# Ethernet.net
KiCad netlist of a schematic drawn in Altium Designer
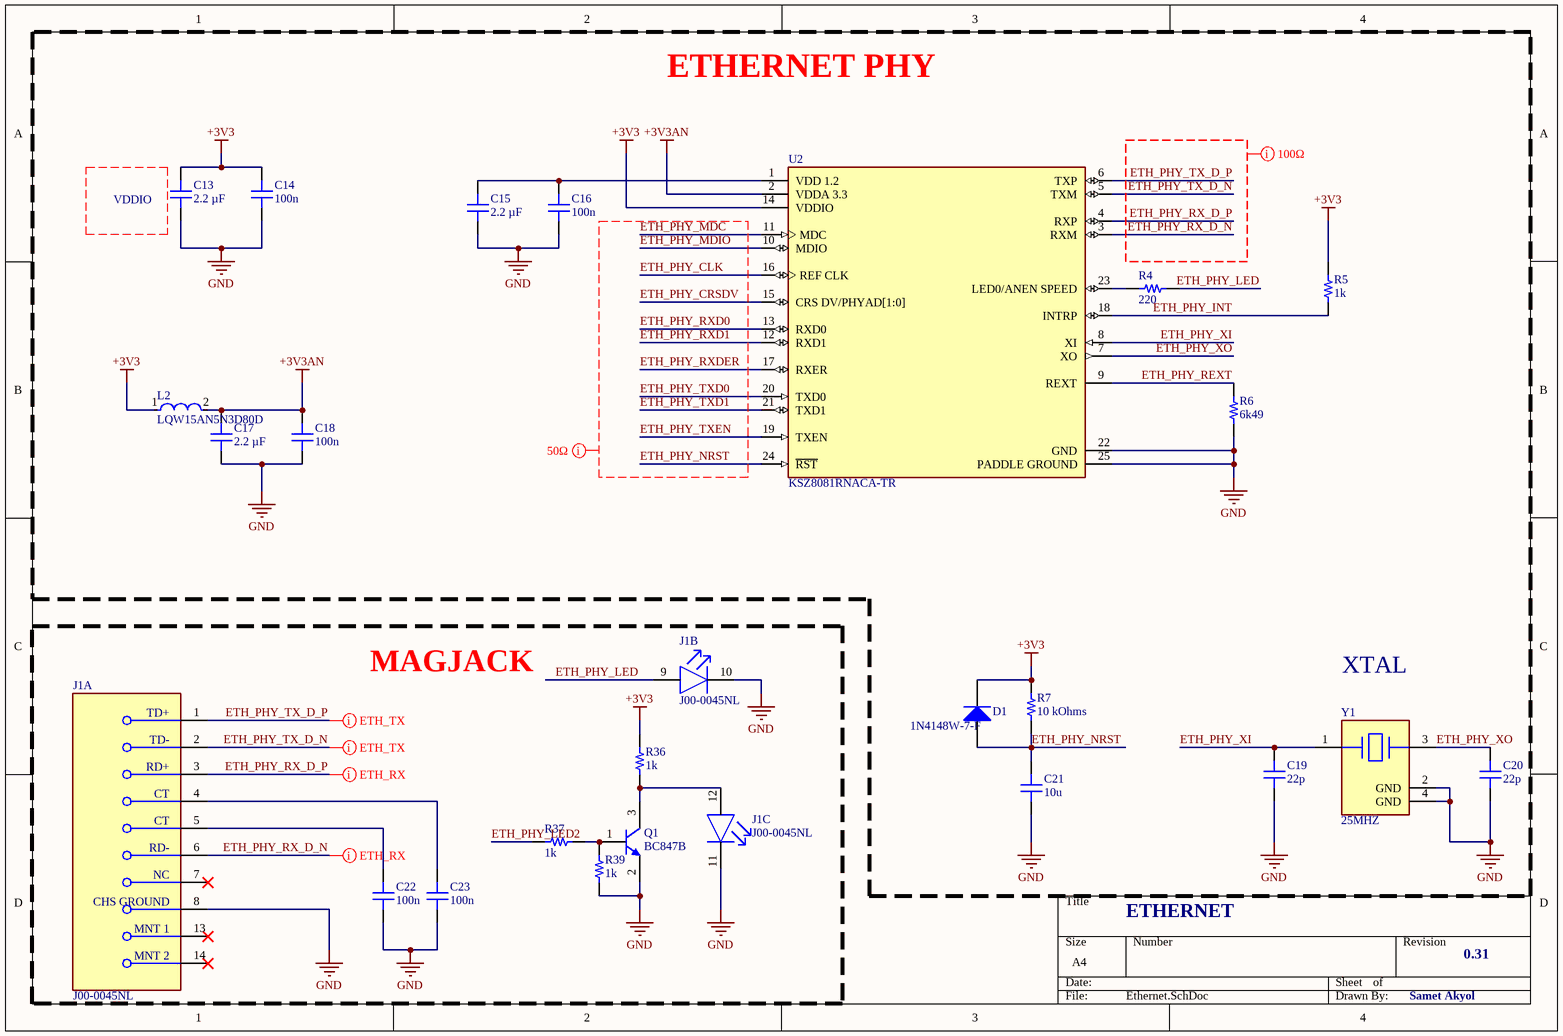
[diagram p0: Ethernet.SchDoc]

(export (version "E")
  (design (tool "Eeschema 10.0.6"))
  (components
    (comp (ref "C13")
      (value "2.2 µF")
      (footprint "CAP 0402_1005")
      (description "CAP CER 2.2UF 16V X5R 0402")
      (fields
        (field (name "PART NUMBER") "CL05A225KO5NQNC")
        (field (name "MANUFACTURER") "Samsung Electro-Mechanics")
      )
      (libsource (lib "Celestial Altium Library - altium_library") (part "Capacitor"))
    )
    (comp (ref "C14")
      (value "100n")
      (footprint "CAP 0402_1005")
      (description "CAP CER 100NF 10V X7R 0402")
      (fields
        (field (name "PART NUMBER") "CL05B104KP5VPNC")
        (field (name "MANUFACTURER") "Samsung Electro-Mechanics")
      )
      (libsource (lib "Celestial Altium Library - altium_library") (part "Capacitor"))
    )
    (comp (ref "C15")
      (value "2.2 µF")
      (footprint "CAP 0402_1005")
      (description "CAP CER 2.2UF 16V X5R 0402")
      (fields
        (field (name "PART NUMBER") "CL05A225KO5NQNC")
        (field (name "MANUFACTURER") "Samsung Electro-Mechanics")
      )
      (libsource (lib "Celestial Altium Library - altium_library") (part "Capacitor"))
    )
    (comp (ref "C16")
      (value "100n")
      (footprint "CAP 0402_1005")
      (description "CAP CER 100NF 10V X7R 0402")
      (fields
        (field (name "PART NUMBER") "CL05B104KP5VPNC")
        (field (name "MANUFACTURER") "Samsung Electro-Mechanics")
      )
      (libsource (lib "Celestial Altium Library - altium_library") (part "Capacitor"))
    )
    (comp (ref "C17")
      (value "2.2 µF")
      (footprint "CAP 0402_1005")
      (description "CAP CER 2.2UF 16V X5R 0402")
      (fields
        (field (name "PART NUMBER") "CL05A225KO5NQNC")
        (field (name "MANUFACTURER") "Samsung Electro-Mechanics")
      )
      (libsource (lib "Celestial Altium Library - altium_library") (part "Capacitor"))
    )
    (comp (ref "C18")
      (value "100n")
      (footprint "CAP 0402_1005")
      (description "CAP CER 100NF 10V X7R 0402")
      (fields
        (field (name "PART NUMBER") "CL05B104KP5VPNC")
        (field (name "MANUFACTURER") "Samsung Electro-Mechanics")
      )
      (libsource (lib "Celestial Altium Library - altium_library") (part "Capacitor"))
    )
    (comp (ref "C19")
      (value "22p")
      (footprint "CAP 0402_1005")
      (description "CAP CER 100NF 10V X7R 0402")
      (fields
        (field (name "PART NUMBER") "CL05B104KP5VPNC")
        (field (name "MANUFACTURER") "Samsung Electro-Mechanics")
      )
      (libsource (lib "Celestial Altium Library - altium_library") (part "Capacitor"))
    )
    (comp (ref "C20")
      (value "22p")
      (footprint "CAP 0402_1005")
      (description "CAP CER 100NF 10V X7R 0402")
      (fields
        (field (name "PART NUMBER") "CL05B104KP5VPNC")
        (field (name "MANUFACTURER") "Samsung Electro-Mechanics")
      )
      (libsource (lib "Celestial Altium Library - altium_library") (part "Capacitor"))
    )
    (comp (ref "C21")
      (value "10u")
      (footprint "CAP 0402_1005")
      (description "CAP CER 2.2UF 16V X5R 0402")
      (fields
        (field (name "PART NUMBER") "CL05A225KO5NQNC")
        (field (name "MANUFACTURER") "Samsung Electro-Mechanics")
      )
      (libsource (lib "Celestial Altium Library - altium_library") (part "Capacitor"))
    )
    (comp (ref "C22")
      (value "100n")
      (footprint "CAP 0402_1005")
      (description "CAP CER 100NF 10V X7R 0402")
      (fields
        (field (name "PART NUMBER") "CL05B104KP5VPNC")
        (field (name "MANUFACTURER") "Samsung Electro-Mechanics")
      )
      (libsource (lib "Celestial Altium Library - altium_library") (part "Capacitor"))
    )
    (comp (ref "C23")
      (value "100n")
      (footprint "CAP 0402_1005")
      (description "CAP CER 100NF 10V X7R 0402")
      (fields
        (field (name "PART NUMBER") "CL05B104KP5VPNC")
        (field (name "MANUFACTURER") "Samsung Electro-Mechanics")
      )
      (libsource (lib "Celestial Altium Library - altium_library") (part "Capacitor"))
    )
    (comp (ref "D1")
      (value "1N4148W-7-F")
      (footprint "DIOD-SOD123-2_V")
      (description "Fast Switching Diode, 100 V, 0.15 A, -65 to 150 degC, 2-Pin?SOD123, RoHS, Tape and Reel")
      (fields (field (name "MANUFACTURER") "DiodesIncorporated"))
      (libsource (lib "Altium Content Vault") (part "D-AK-2"))
    )
    (comp (ref "J1")
      (value "J00-0045NL")
      (footprint "FP-J00-0045NL-MFG")
      (description "CONN JACK 1PORT 100 BASE-TX PCB")
      (libsource (lib "Altium Content Vault") (part "9e414223d7443300137682b695b44b7"))
    )
    (comp (ref "L2")
      (value "LQW15AN5N3D80D")
      (footprint "FP-LQW15AN_80-MFG")
      (description "Wire Wound RF Inductor 5.3nH ±0.5nH 1770mA 0.04Ω 0402 (1005)")
      (libsource (lib "Altium Content Vault") (part "725321dda6339637d4d059423bc1c3c"))
    )
    (comp (ref "Q1")
      (value "BC847B")
      (footprint "INF-SOT23_M")
      (description "NPN Silicon AF Transistor, 45 V VCEO, 100 mA IC, SOT23, Reel, Green")
      (fields (field (name "MANUFACTURER") "Infineon"))
      (libsource (lib "Altium Content Vault") (part "INF-BJTNPN-BEC-3"))
    )
    (comp (ref "R4")
      (value "220")
      (footprint "RES 0402_1005")
      (description "RES SMD 1K OHM 0.1% 1/16W 0402")
      (fields
        (field (name "PART NUMBER") "CPF0402B1K0E")
        (field (name "MANUFACTURER") "TE Connectivity Passive Product")
      )
      (libsource (lib "Celestial Altium Library - altium_library") (part "Resistor"))
    )
    (comp (ref "R5")
      (value "1k")
      (footprint "RES 0402_1005")
      (description "RES SMD 1K OHM 0.1% 1/16W 0402")
      (fields
        (field (name "PART NUMBER") "CPF0402B1K0E")
        (field (name "MANUFACTURER") "TE Connectivity Passive Product")
      )
      (libsource (lib "Celestial Altium Library - altium_library") (part "Resistor"))
    )
    (comp (ref "R6")
      (value "6k49")
      (footprint "RES 0402_1005")
      (description "RES SMD 1K OHM 0.1% 1/16W 0402")
      (fields
        (field (name "PART NUMBER") "CPF0402B1K0E")
        (field (name "MANUFACTURER") "TE Connectivity Passive Product")
      )
      (libsource (lib "Celestial Altium Library - altium_library") (part "Resistor"))
    )
    (comp (ref "R7")
      (value "10 kOhms")
      (footprint "RES 0402_1005")
      (description "RES 10K OHM 0.1% 1/10W 0402")
      (fields
        (field (name "PART NUMBER") "RP73PF1E10KBTD")
        (field (name "MANUFACTURER") "TE Connectivity Passive Product")
      )
      (libsource (lib "Celestial Altium Library - altium_library") (part "Resistor"))
    )
    (comp (ref "R36")
      (value "1k")
      (footprint "RES 0402_1005")
      (description "RES SMD 1K OHM 0.1% 1/16W 0402")
      (fields
        (field (name "PART NUMBER") "CPF0402B1K0E")
        (field (name "MANUFACTURER") "TE Connectivity Passive Product")
      )
      (libsource (lib "Celestial Altium Library - altium_library") (part "Resistor"))
    )
    (comp (ref "R37")
      (value "1k")
      (footprint "RES 0402_1005")
      (description "RES SMD 1K OHM 0.1% 1/16W 0402")
      (fields
        (field (name "PART NUMBER") "CPF0402B1K0E")
        (field (name "MANUFACTURER") "TE Connectivity Passive Product")
      )
      (libsource (lib "Celestial Altium Library - altium_library") (part "Resistor"))
    )
    (comp (ref "R39")
      (value "1k")
      (footprint "RES 0402_1005")
      (description "RES SMD 1K OHM 0.1% 1/16W 0402")
      (fields
        (field (name "PART NUMBER") "CPF0402B1K0E")
        (field (name "MANUFACTURER") "TE Connectivity Passive Product")
      )
      (libsource (lib "Celestial Altium Library - altium_library") (part "Resistor"))
    )
    (comp (ref "U2")
      (value "KSZ8081RNACA-TR")
      (footprint "FP-QFN44-24LD-PL-1-MFG")
      (description "IC TRANSCEIVER FULL 1/1 24QFN")
      (fields
        (field (name "MANUFACTURER") "Microchip")
        (field (name "OCTOPART") "https://octopart.com/ksz8081rnaca-tr-microchip-66799960")
      )
      (libsource (lib "Altium Content Vault") (part "db19a252711fc409187aecce7b8462c"))
    )
    (comp (ref "Y1")
      (value "25MHZ")
      (footprint "FP-ABM8G-MFG")
      (description "Crystal 25MHz ±20ppm (Tol) ±30ppm (Stability) 18pF FUND 60Ω 4-Pin SMD T/R")
      (fields (field (name "TOLERANCE") "20ppm"))
      (libsource (lib "Altium Content Vault") (part "48e526d86b7f2615d98721063c72f49"))
    )
  )
  (nets
    (net (code "1") (name "+3V3") (class "Default")
      (node (ref "C13") (pin "2") (pinfunction "2_2") (pintype "passive"))
      (node (ref "C14") (pin "2") (pinfunction "2_2") (pintype "passive"))
      (node (ref "D1") (pin "2") (pinfunction "K_2") (pintype "passive"))
      (node (ref "L2") (pin "1") (pinfunction "1_1") (pintype "passive"))
      (node (ref "R36") (pin "1") (pinfunction "1_1") (pintype "passive"))
      (node (ref "R5") (pin "2") (pinfunction "2_2") (pintype "passive"))
      (node (ref "R7") (pin "2") (pinfunction "2_2") (pintype "passive"))
      (node (ref "U2") (pin "14") (pinfunction "VDDIO_14") (pintype "power_in"))
    )
    (net (code "2") (name "+3V3AN") (class "Default")
      (node (ref "C17") (pin "2") (pinfunction "2_2") (pintype "passive"))
      (node (ref "C18") (pin "2") (pinfunction "2_2") (pintype "passive"))
      (node (ref "L2") (pin "2") (pinfunction "2_2") (pintype "passive"))
      (node (ref "U2") (pin "2") (pinfunction "VDDA_3.3_2") (pintype "power_in"))
    )
    (net (code "3") (name "/ETH_PHY_CLK") (class "Default")
      (node (ref "U2") (pin "16") (pinfunction "REF_CLK_16") (pintype "bidirectional"))
    )
    (net (code "4") (name "/ETH_PHY_CRSDV") (class "Default")
      (node (ref "U2") (pin "15") (pinfunction "CRS_DV/PHYAD[1:0]_15") (pintype "bidirectional"))
    )
    (net (code "5") (name "/ETH_PHY_INT") (class "Default")
      (node (ref "R5") (pin "1") (pinfunction "1_1") (pintype "passive"))
      (node (ref "U2") (pin "18") (pinfunction "INTRP_18") (pintype "bidirectional"))
    )
    (net (code "6") (name "/ETH_PHY_LED") (class "Default")
      (node (ref "J1") (pin "9") (pinfunction "GREEN_A_9") (pintype "passive"))
      (node (ref "R4") (pin "1") (pinfunction "1_1") (pintype "passive"))
    )
    (net (code "7") (name "/ETH_PHY_LED2") (class "Default")
      (node (ref "R37") (pin "2") (pinfunction "2_2") (pintype "passive"))
    )
    (net (code "8") (name "/ETH_PHY_MDC") (class "Default")
      (node (ref "U2") (pin "11") (pinfunction "MDC_11") (pintype "input"))
    )
    (net (code "9") (name "/ETH_PHY_MDIO") (class "Default")
      (node (ref "U2") (pin "10") (pinfunction "MDIO_10") (pintype "bidirectional"))
    )
    (net (code "10") (name "/ETH_PHY_NRST") (class "Default")
      (node (ref "C21") (pin "2") (pinfunction "2_2") (pintype "passive"))
      (node (ref "D1") (pin "1") (pinfunction "A_1") (pintype "passive"))
      (node (ref "R7") (pin "1") (pinfunction "1_1") (pintype "passive"))
      (node (ref "U2") (pin "24") (pinfunction "~{RST}_24") (pintype "input"))
    )
    (net (code "11") (name "/ETH_PHY_REXT") (class "Default")
      (node (ref "R6") (pin "2") (pinfunction "2_2") (pintype "passive"))
      (node (ref "U2") (pin "9") (pinfunction "REXT_9") (pintype "passive"))
    )
    (net (code "12") (name "/ETH_PHY_RXD0") (class "Default")
      (node (ref "U2") (pin "13") (pinfunction "RXD0_13") (pintype "bidirectional"))
    )
    (net (code "13") (name "/ETH_PHY_RXD1") (class "Default")
      (node (ref "U2") (pin "12") (pinfunction "RXD1_12") (pintype "bidirectional"))
    )
    (net (code "14") (name "/ETH_PHY_RXDER") (class "Default")
      (node (ref "U2") (pin "17") (pinfunction "RXER_17") (pintype "bidirectional"))
    )
    (net (code "15") (name "/ETH_PHY_RX_D_N") (class "Default")
      (node (ref "J1") (pin "6") (pinfunction "RD-_6") (pintype "passive"))
      (node (ref "U2") (pin "3") (pinfunction "RXM_3") (pintype "bidirectional"))
    )
    (net (code "16") (name "/ETH_PHY_RX_D_P") (class "Default")
      (node (ref "J1") (pin "3") (pinfunction "RD+_3") (pintype "passive"))
      (node (ref "U2") (pin "4") (pinfunction "RXP_4") (pintype "bidirectional"))
    )
    (net (code "17") (name "/ETH_PHY_TXD0") (class "Default")
      (node (ref "U2") (pin "20") (pinfunction "TXD0_20") (pintype "input"))
    )
    (net (code "18") (name "/ETH_PHY_TXD1") (class "Default")
      (node (ref "U2") (pin "21") (pinfunction "TXD1_21") (pintype "bidirectional"))
    )
    (net (code "19") (name "/ETH_PHY_TXEN") (class "Default")
      (node (ref "U2") (pin "19") (pinfunction "TXEN_19") (pintype "input"))
    )
    (net (code "20") (name "/ETH_PHY_TX_D_N") (class "Default")
      (node (ref "J1") (pin "2") (pinfunction "TD-_2") (pintype "passive"))
      (node (ref "U2") (pin "5") (pinfunction "TXM_5") (pintype "bidirectional"))
    )
    (net (code "21") (name "/ETH_PHY_TX_D_P") (class "Default")
      (node (ref "J1") (pin "1") (pinfunction "TD+_1") (pintype "passive"))
      (node (ref "U2") (pin "6") (pinfunction "TXP_6") (pintype "bidirectional"))
    )
    (net (code "22") (name "/ETH_PHY_XI") (class "Default")
      (node (ref "C19") (pin "2") (pinfunction "2_2") (pintype "passive"))
      (node (ref "U2") (pin "8") (pinfunction "XI_8") (pintype "input"))
      (node (ref "Y1") (pin "1") (pinfunction "1_1") (pintype "passive"))
    )
    (net (code "23") (name "/ETH_PHY_XO") (class "Default")
      (node (ref "C20") (pin "2") (pinfunction "2_2") (pintype "passive"))
      (node (ref "U2") (pin "7") (pinfunction "XO_7") (pintype "output"))
      (node (ref "Y1") (pin "3") (pinfunction "3_3") (pintype "passive"))
    )
    (net (code "24") (name "GND") (class "Default")
      (node (ref "C13") (pin "1") (pinfunction "1_1") (pintype "passive"))
      (node (ref "C14") (pin "1") (pinfunction "1_1") (pintype "passive"))
      (node (ref "C15") (pin "1") (pinfunction "1_1") (pintype "passive"))
      (node (ref "C16") (pin "1") (pinfunction "1_1") (pintype "passive"))
      (node (ref "C17") (pin "1") (pinfunction "1_1") (pintype "passive"))
      (node (ref "C18") (pin "1") (pinfunction "1_1") (pintype "passive"))
      (node (ref "C19") (pin "1") (pinfunction "1_1") (pintype "passive"))
      (node (ref "C20") (pin "1") (pinfunction "1_1") (pintype "passive"))
      (node (ref "C21") (pin "1") (pinfunction "1_1") (pintype "passive"))
      (node (ref "C22") (pin "1") (pinfunction "1_1") (pintype "passive"))
      (node (ref "C23") (pin "1") (pinfunction "1_1") (pintype "passive"))
      (node (ref "J1") (pin "10") (pinfunction "GREEN_C_10") (pintype "passive"))
      (node (ref "J1") (pin "11") (pinfunction "YELLOW_CATHODE_11") (pintype "passive"))
      (node (ref "J1") (pin "8") (pinfunction "CHS_GROUND_8") (pintype "passive"))
      (node (ref "Q1") (pin "2") (pinfunction "E_2") (pintype "passive"))
      (node (ref "R39") (pin "1") (pinfunction "1_1") (pintype "passive"))
      (node (ref "R6") (pin "1") (pinfunction "1_1") (pintype "passive"))
      (node (ref "U2") (pin "22") (pinfunction "GND_22") (pintype "power_in"))
      (node (ref "U2") (pin "25") (pinfunction "PADDLE_GROUND_25") (pintype "power_in"))
      (node (ref "Y1") (pin "2") (pinfunction "GND_2") (pintype "power_in"))
      (node (ref "Y1") (pin "4") (pinfunction "GND_4") (pintype "power_in"))
    )
    (net (code "25") (name "Net-(C22-Pad2)") (class "Default")
      (node (ref "C22") (pin "2") (pinfunction "2_2") (pintype "passive"))
      (node (ref "J1") (pin "5") (pinfunction "CT_5") (pintype "passive"))
    )
    (net (code "26") (name "Net-(C23-Pad2)") (class "Default")
      (node (ref "C23") (pin "2") (pinfunction "2_2") (pintype "passive"))
      (node (ref "J1") (pin "4") (pinfunction "CT_4") (pintype "passive"))
    )
    (net (code "27") (name "Net-(J1C-YELLOW_ANODE)") (class "Default")
      (node (ref "J1") (pin "12") (pinfunction "YELLOW_ANODE_12") (pintype "passive"))
      (node (ref "Q1") (pin "3") (pinfunction "C_3") (pintype "passive"))
      (node (ref "R36") (pin "2") (pinfunction "2_2") (pintype "passive"))
    )
    (net (code "28") (name "Net-(Q1-B)") (class "Default")
      (node (ref "Q1") (pin "1") (pinfunction "B_1") (pintype "passive"))
      (node (ref "R37") (pin "1") (pinfunction "1_1") (pintype "passive"))
      (node (ref "R39") (pin "2") (pinfunction "2_2") (pintype "passive"))
    )
    (net (code "29") (name "Net-(U2-LED0{slash}ANEN_SPEED)") (class "Default")
      (node (ref "R4") (pin "2") (pinfunction "2_2") (pintype "passive"))
      (node (ref "U2") (pin "23") (pinfunction "LED0/ANEN_SPEED_23") (pintype "bidirectional"))
    )
    (net (code "30") (name "Net-(U2-VDD_1.2)") (class "Default")
      (node (ref "C15") (pin "2") (pinfunction "2_2") (pintype "passive"))
      (node (ref "C16") (pin "2") (pinfunction "2_2") (pintype "passive"))
      (node (ref "U2") (pin "1") (pinfunction "VDD_1.2_1") (pintype "power_in"))
    )
    (net (code "31") (name "unconnected-(J1A-MNT_1-Pad13)") (class "Default")
      (node (ref "J1") (pin "13") (pinfunction "MNT_1_13") (pintype "passive+no_connect"))
    )
    (net (code "32") (name "unconnected-(J1A-MNT_2-Pad14)") (class "Default")
      (node (ref "J1") (pin "14") (pinfunction "MNT_2_14") (pintype "passive+no_connect"))
    )
    (net (code "33") (name "unconnected-(J1A-NC-Pad7)") (class "Default")
      (node (ref "J1") (pin "7") (pinfunction "NC_7") (pintype "passive+no_connect"))
    )
  )
)
